# MCU.net
KiCad netlist of a schematic drawn in Altium Designer
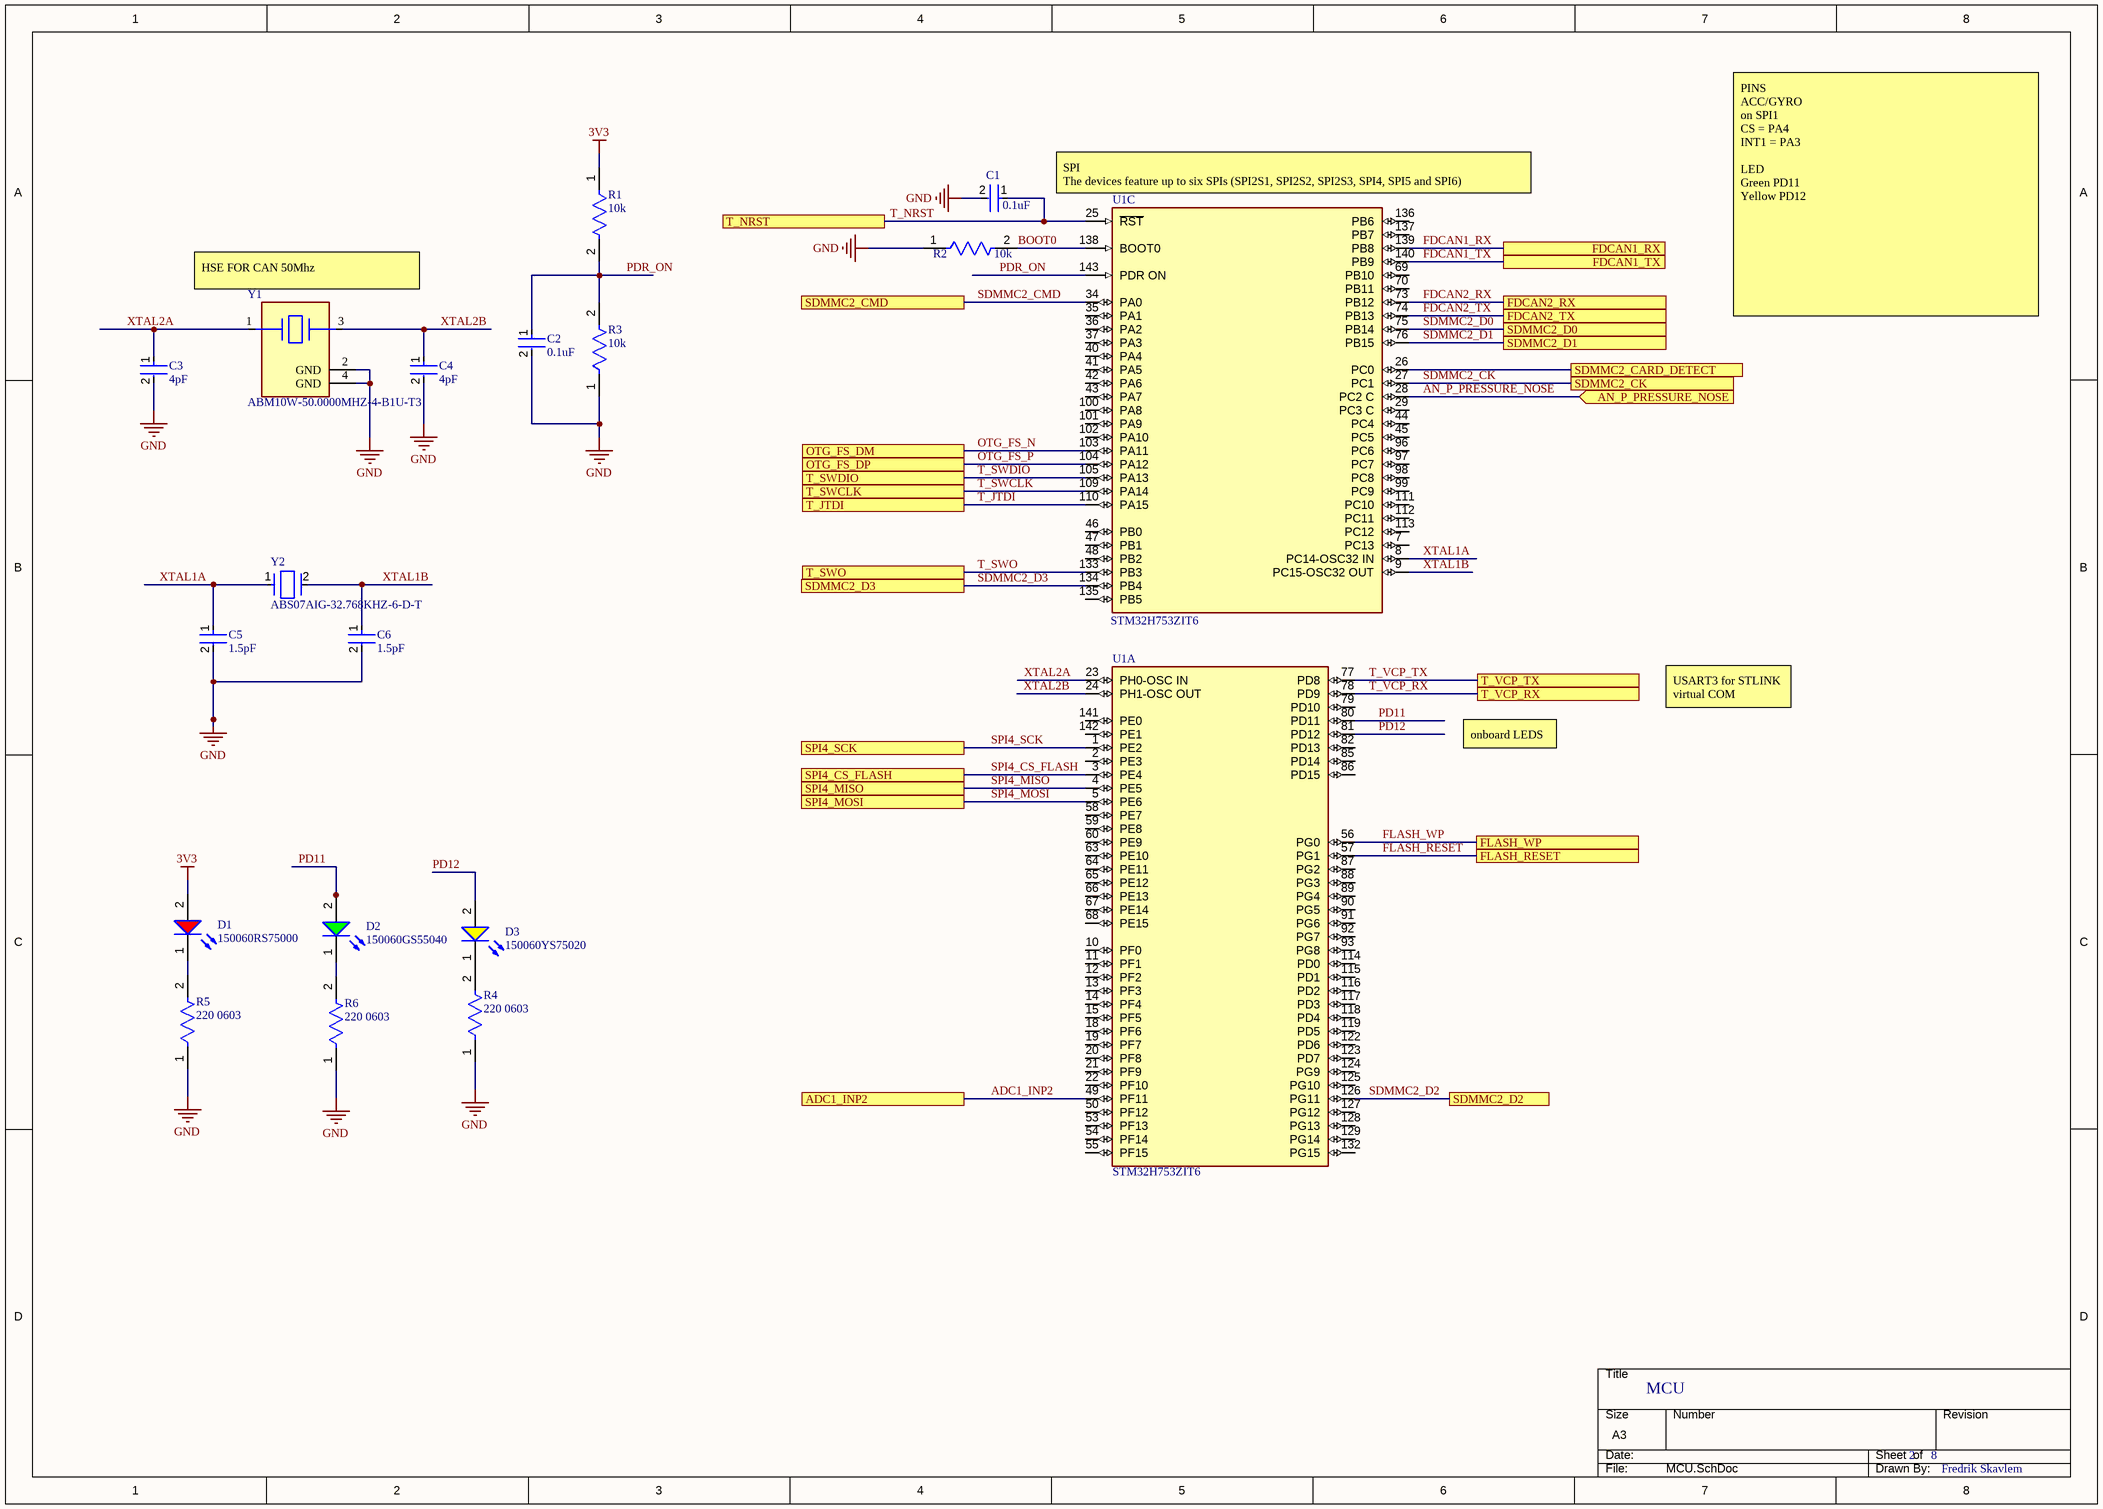
[diagram p0: MCU.SchDoc]

(export (version "E")
  (design (tool "Eeschema 10.0.6"))
  (components
    (comp (ref "C1")
      (value "0.1uF")
      (footprint "FP-CL10-IPC_C")
      (description "Cap Ceramic 100nF 16V X7R ±10% Pad SMD 0603 +125°C T/R\r\nCL10B104KO8WPNC")
      (fields (field (name "TOLERANCE") "10%"))
      (libsource (lib "Altium Content Vault") (part "b4654b650e69147ec39a6b967a45e02"))
    )
    (comp (ref "C2")
      (value "0.1uF")
      (footprint "FP-CL10-IPC_C")
      (description "Cap Ceramic 100nF 16V X7R ±10% Pad SMD 0603 +125°C T/R\r\nCL10B104KO8WPNC")
      (fields (field (name "TOLERANCE") "10%"))
      (libsource (lib "Altium Content Vault") (part "b4654b650e69147ec39a6b967a45e02"))
    )
    (comp (ref "C3")
      (value "4pF")
      (footprint "FP-GQM187-0_15-IPC_B")
      (description "GQM1875C2E4R0BB12D\r\nCeramic Capacitor 4pF ±0.1pF 250VDC C0G 0603 Paper T/R")
      (libsource (lib "Altium Content Vault") (part "02cd4be3c70576c341d710602a673aa"))
    )
    (comp (ref "C4")
      (value "4pF")
      (footprint "FP-GQM187-0_15-IPC_B")
      (description "GQM1875C2E4R0BB12D\r\nCeramic Capacitor 4pF ±0.1pF 250VDC C0G 0603 Paper T/R")
      (libsource (lib "Altium Content Vault") (part "02cd4be3c70576c341d710602a673aa"))
    )
    (comp (ref "C5")
      (value "1.5pF")
      (footprint "FP-C0603C-CF-IPC_C")
      (description "C0603 1.5 pF X8R 30ppm/°C 0.1 pF 25 V\r\nC0603C159B3HACTU")
      (fields
        (field (name "OCTOPART") "https://octopart.com/c0603c159b3hactu-kemet-88725126")
        (field (name "MANUFACTURER") "KEMET")
      )
      (libsource (lib "Altium Content Vault") (part "b4654b650e69147ec39a6b967a45e02"))
    )
    (comp (ref "C6")
      (value "1.5pF")
      (footprint "FP-C0603C-CF-MFG")
      (description "C0603 1.5 pF X8R 30ppm/°C 0.1 pF 25 V\r\nC0603C159B3HACTU")
      (fields
        (field (name "OCTOPART") "https://octopart.com/c0603c159b3hactu-kemet-88725126")
        (field (name "MANUFACTURER") "KEMET")
      )
      (libsource (lib "Altium Content Vault") (part "b4654b650e69147ec39a6b967a45e02"))
    )
    (comp (ref "D1")
      (value "150060RS75000")
      (footprint "WL-SMCW_0603_150060xx75000")
      (libsource (lib "Altium Content Vault") (part "LED_Red_2A-1K"))
    )
    (comp (ref "D2")
      (value "150060GS55040")
      (footprint "WL-SMCD_0603")
      (description "150060GS55040 WL-SMCD SMT Mono-color Chip LED Diffused")
      (libsource (lib "Altium Content Vault") (part "LED_Green_2A-1K"))
    )
    (comp (ref "D3")
      (value "150060YS75020")
      (footprint "WL-SMCW_0603_150060xx75020")
      (description "WL-SMCW SMT Mono-Color Chip LED Waterclear super f")
      (libsource (lib "Altium Content Vault") (part "LED_Yellow_2A-1K"))
    )
    (comp (ref "R1")
      (value "10k")
      (footprint "FP-RT0603-IPC_C")
      (description "RES SMD 10K OHM 1% 1/10W 0603\r\nRT0603FRE0710KL")
      (fields
        (field (name "MANUFACTURER") "Yageo")
        (field (name "OCTOPART") "https://octopart.com/rt0603fre0710kl-yageo-40009243")
      )
      (libsource (lib "Altium Content Vault") (part "1029c3af85768c4190bb7ad29bc67b5"))
    )
    (comp (ref "R2")
      (value "10k")
      (footprint "FP-RT0603-IPC_C")
      (description "RES SMD 10K OHM 1% 1/10W 0603\r\nRT0603FRE0710KL")
      (fields
        (field (name "MANUFACTURER") "Yageo")
        (field (name "OCTOPART") "https://octopart.com/rt0603fre0710kl-yageo-40009243")
      )
      (libsource (lib "Altium Content Vault") (part "1029c3af85768c4190bb7ad29bc67b5"))
    )
    (comp (ref "R3")
      (value "10k")
      (footprint "FP-RT0603-IPC_C")
      (description "RES SMD 10K OHM 1% 1/10W 0603\r\nRT0603FRE0710KL")
      (fields
        (field (name "MANUFACTURER") "Yageo")
        (field (name "OCTOPART") "https://octopart.com/rt0603fre0710kl-yageo-40009243")
      )
      (libsource (lib "Altium Content Vault") (part "1029c3af85768c4190bb7ad29bc67b5"))
    )
    (comp (ref "R4")
      (value "220 0603")
      (footprint "FP-AF0603-IPC_C")
      (description "AF0603JR-07220RL Anti-Sulfurated Chip Resistors Automotive Grade 220Ω 5% 100ppm/°C 0603")
      (fields (field (name "TOLERANCE") "5%"))
      (libsource (lib "Altium Content Vault") (part "1029c3af85768c4190bb7ad29bc67b5"))
    )
    (comp (ref "R5")
      (value "220 0603")
      (footprint "FP-AF0603-IPC_C")
      (description "AF0603JR-07220RL Anti-Sulfurated Chip Resistors Automotive Grade 220Ω 5% 100ppm/°C 0603")
      (fields (field (name "TOLERANCE") "5%"))
      (libsource (lib "Altium Content Vault") (part "1029c3af85768c4190bb7ad29bc67b5"))
    )
    (comp (ref "R6")
      (value "220 0603")
      (footprint "FP-AF0603-IPC_C")
      (description "AF0603JR-07220RL Anti-Sulfurated Chip Resistors Automotive Grade 220Ω 5% 100ppm/°C 0603")
      (fields (field (name "TOLERANCE") "5%"))
      (libsource (lib "Altium Content Vault") (part "1029c3af85768c4190bb7ad29bc67b5"))
    )
    (comp (ref "U1")
      (value "STM32H753ZIT6")
      (footprint "FP-LQFP144-1A-MFG")
      (description "LQFP 144 20X20X1.4 2")
      (fields
        (field (name "MANUFACTURER") "STMicroelectronics")
        (field (name "OCTOPART") "https://octopart.com/stm32h753zit6-stmicroelectronics-87879771")
      )
      (libsource (lib "Altium Content Vault") (part "eeed45f8b0ec3d8db28e558541eef73"))
    )
    (comp (ref "Y1")
      (value "ABM10W-50.0000MHZ-4-B1U-T3")
      (footprint "FP-ABM10W-MFG")
      (description "Crystal 50MHz ±10ppm 4pF SMD-4 2.5mm x 2mm")
      (libsource (lib "Altium Content Vault") (part "5d53a81b36bb19e40e9e80ec3e46f97"))
    )
    (comp (ref "Y2")
      (value "ABS07AIG-32.768KHZ-6-D-T")
      (footprint "FP-ABS07AIG-MFG")
      (description "Crystal 32.768kHz ±20ppm (Tol) 6pF FUND 70kΩ Automotive 2-Pin Mini-CSMD T/R")
      (libsource (lib "Altium Content Vault") (part "c23a69dc6c9e2f18f2079038eb95dd1"))
    )
  )
  (nets
    (net (code "1") (name "/ADC1_INP2") (class "Default")
      (node (ref "U1") (pin "49") (pinfunction "PF11_49") (pintype "bidirectional"))
    )
    (net (code "2") (name "/AN_P_PRESSURE_NOSE") (class "Default")
      (node (ref "U1") (pin "28") (pinfunction "PC2_C_28") (pintype "bidirectional"))
    )
    (net (code "3") (name "/BOOT0") (class "Default")
      (node (ref "R2") (pin "2") (pinfunction "2_2") (pintype "passive"))
      (node (ref "U1") (pin "138") (pinfunction "BOOT0_138") (pintype "input"))
    )
    (net (code "4") (name "/FDCAN1_RX") (class "Default")
      (node (ref "U1") (pin "139") (pinfunction "PB8_139") (pintype "bidirectional"))
    )
    (net (code "5") (name "/FDCAN1_TX") (class "Default")
      (node (ref "U1") (pin "140") (pinfunction "PB9_140") (pintype "bidirectional"))
    )
    (net (code "6") (name "/FDCAN2_RX") (class "Default")
      (node (ref "U1") (pin "73") (pinfunction "PB12_73") (pintype "bidirectional"))
    )
    (net (code "7") (name "/FDCAN2_TX") (class "Default")
      (node (ref "U1") (pin "74") (pinfunction "PB13_74") (pintype "bidirectional"))
    )
    (net (code "8") (name "/FLASH_RESET") (class "Default")
      (node (ref "U1") (pin "57") (pinfunction "PG1_57") (pintype "bidirectional"))
    )
    (net (code "9") (name "/FLASH_WP") (class "Default")
      (node (ref "U1") (pin "56") (pinfunction "PG0_56") (pintype "bidirectional"))
    )
    (net (code "10") (name "/OTG_FS_N") (class "Default")
      (node (ref "U1") (pin "103") (pinfunction "PA11_103") (pintype "bidirectional"))
    )
    (net (code "11") (name "/OTG_FS_P") (class "Default")
      (node (ref "U1") (pin "104") (pinfunction "PA12_104") (pintype "bidirectional"))
    )
    (net (code "12") (name "/PD11") (class "Default")
      (node (ref "D2") (pin "2") (pinfunction "A_2") (pintype "passive"))
      (node (ref "U1") (pin "80") (pinfunction "PD11_80") (pintype "bidirectional"))
    )
    (net (code "13") (name "/PD12") (class "Default")
      (node (ref "D3") (pin "2") (pinfunction "A_2") (pintype "passive"))
      (node (ref "U1") (pin "81") (pinfunction "PD12_81") (pintype "bidirectional"))
    )
    (net (code "14") (name "/PDR_ON") (class "Default")
      (node (ref "C2") (pin "1") (pinfunction "1_1") (pintype "passive"))
      (node (ref "R1") (pin "2") (pinfunction "2_2") (pintype "passive"))
      (node (ref "R3") (pin "2") (pinfunction "2_2") (pintype "passive"))
      (node (ref "U1") (pin "143") (pinfunction "PDR_ON_143") (pintype "input"))
    )
    (net (code "15") (name "/SDMMC2_CARD_DETECT") (class "Default")
      (node (ref "U1") (pin "26") (pinfunction "PC0_26") (pintype "bidirectional"))
    )
    (net (code "16") (name "/SDMMC2_CK") (class "Default")
      (node (ref "U1") (pin "27") (pinfunction "PC1_27") (pintype "bidirectional"))
    )
    (net (code "17") (name "/SDMMC2_CMD") (class "Default")
      (node (ref "U1") (pin "34") (pinfunction "PA0_34") (pintype "bidirectional"))
    )
    (net (code "18") (name "/SDMMC2_D0") (class "Default")
      (node (ref "U1") (pin "75") (pinfunction "PB14_75") (pintype "bidirectional"))
    )
    (net (code "19") (name "/SDMMC2_D1") (class "Default")
      (node (ref "U1") (pin "76") (pinfunction "PB15_76") (pintype "bidirectional"))
    )
    (net (code "20") (name "/SDMMC2_D2") (class "Default")
      (node (ref "U1") (pin "126") (pinfunction "PG11_126") (pintype "bidirectional"))
    )
    (net (code "21") (name "/SDMMC2_D3") (class "Default")
      (node (ref "U1") (pin "134") (pinfunction "PB4_134") (pintype "bidirectional"))
    )
    (net (code "22") (name "/SPI4_CS_FLASH") (class "Default")
      (node (ref "U1") (pin "3") (pinfunction "PE4_3") (pintype "bidirectional"))
    )
    (net (code "23") (name "/SPI4_MISO") (class "Default")
      (node (ref "U1") (pin "4") (pinfunction "PE5_4") (pintype "bidirectional"))
    )
    (net (code "24") (name "/SPI4_MOSI") (class "Default")
      (node (ref "U1") (pin "5") (pinfunction "PE6_5") (pintype "bidirectional"))
    )
    (net (code "25") (name "/SPI4_SCK") (class "Default")
      (node (ref "U1") (pin "1") (pinfunction "PE2_1") (pintype "bidirectional"))
    )
    (net (code "26") (name "/T_JTDI") (class "Default")
      (node (ref "U1") (pin "110") (pinfunction "PA15_110") (pintype "bidirectional"))
    )
    (net (code "27") (name "/T_NRST") (class "Default")
      (node (ref "C1") (pin "1") (pinfunction "1_1") (pintype "passive"))
      (node (ref "U1") (pin "25") (pinfunction "~{RST}_25") (pintype "input"))
    )
    (net (code "28") (name "/T_SWCLK") (class "Default")
      (node (ref "U1") (pin "109") (pinfunction "PA14_109") (pintype "bidirectional"))
    )
    (net (code "29") (name "/T_SWDIO") (class "Default")
      (node (ref "U1") (pin "105") (pinfunction "PA13_105") (pintype "bidirectional"))
    )
    (net (code "30") (name "/T_SWO") (class "Default")
      (node (ref "U1") (pin "133") (pinfunction "PB3_133") (pintype "bidirectional"))
    )
    (net (code "31") (name "/T_VCP_RX") (class "Default")
      (node (ref "U1") (pin "78") (pinfunction "PD9_78") (pintype "bidirectional"))
    )
    (net (code "32") (name "/T_VCP_TX") (class "Default")
      (node (ref "U1") (pin "77") (pinfunction "PD8_77") (pintype "bidirectional"))
    )
    (net (code "33") (name "/XTAL1A") (class "Default")
      (node (ref "C5") (pin "1") (pinfunction "1_1") (pintype "passive"))
      (node (ref "U1") (pin "8") (pinfunction "PC14-OSC32_IN_8") (pintype "bidirectional"))
      (node (ref "Y2") (pin "1") (pinfunction "1_1") (pintype "passive"))
    )
    (net (code "34") (name "/XTAL1B") (class "Default")
      (node (ref "C6") (pin "1") (pinfunction "1_1") (pintype "passive"))
      (node (ref "U1") (pin "9") (pinfunction "PC15-OSC32_OUT_9") (pintype "bidirectional"))
      (node (ref "Y2") (pin "2") (pinfunction "2_2") (pintype "passive"))
    )
    (net (code "35") (name "/XTAL2A") (class "Default")
      (node (ref "C3") (pin "1") (pinfunction "1_1") (pintype "passive"))
      (node (ref "U1") (pin "23") (pinfunction "PH0-OSC_IN_23") (pintype "bidirectional"))
      (node (ref "Y1") (pin "1") (pinfunction "1_1") (pintype "passive"))
    )
    (net (code "36") (name "/XTAL2B") (class "Default")
      (node (ref "C4") (pin "1") (pinfunction "1_1") (pintype "passive"))
      (node (ref "U1") (pin "24") (pinfunction "PH1-OSC_OUT_24") (pintype "bidirectional"))
      (node (ref "Y1") (pin "3") (pinfunction "3_3") (pintype "passive"))
    )
    (net (code "37") (name "3V3") (class "Default")
      (node (ref "D1") (pin "2") (pinfunction "A_2") (pintype "passive"))
      (node (ref "R1") (pin "1") (pinfunction "1_1") (pintype "passive"))
    )
    (net (code "38") (name "GND") (class "Default")
      (node (ref "C1") (pin "2") (pinfunction "2_2") (pintype "passive"))
      (node (ref "C2") (pin "2") (pinfunction "2_2") (pintype "passive"))
      (node (ref "C3") (pin "2") (pinfunction "2_2") (pintype "passive"))
      (node (ref "C4") (pin "2") (pinfunction "2_2") (pintype "passive"))
      (node (ref "C5") (pin "2") (pinfunction "2_2") (pintype "passive"))
      (node (ref "C6") (pin "2") (pinfunction "2_2") (pintype "passive"))
      (node (ref "R2") (pin "1") (pinfunction "1_1") (pintype "passive"))
      (node (ref "R3") (pin "1") (pinfunction "1_1") (pintype "passive"))
      (node (ref "R4") (pin "1") (pinfunction "1_1") (pintype "passive"))
      (node (ref "R5") (pin "1") (pinfunction "1_1") (pintype "passive"))
      (node (ref "R6") (pin "1") (pinfunction "1_1") (pintype "passive"))
      (node (ref "Y1") (pin "2") (pinfunction "GND_2") (pintype "power_in"))
      (node (ref "Y1") (pin "4") (pinfunction "GND_4") (pintype "power_in"))
    )
    (net (code "39") (name "Net-(D1-K)") (class "Default")
      (node (ref "D1") (pin "1") (pinfunction "K_1") (pintype "passive"))
      (node (ref "R5") (pin "2") (pinfunction "2_2") (pintype "passive"))
    )
    (net (code "40") (name "Net-(D2-K)") (class "Default")
      (node (ref "D2") (pin "1") (pinfunction "K_1") (pintype "passive"))
      (node (ref "R6") (pin "2") (pinfunction "2_2") (pintype "passive"))
    )
    (net (code "41") (name "Net-(D3-K)") (class "Default")
      (node (ref "D3") (pin "1") (pinfunction "K_1") (pintype "passive"))
      (node (ref "R4") (pin "2") (pinfunction "2_2") (pintype "passive"))
    )
    (net (code "42") (name "unconnected-(U1A-PD0-Pad114)") (class "Default")
      (node (ref "U1") (pin "114") (pinfunction "PD0_114") (pintype "bidirectional"))
    )
    (net (code "43") (name "unconnected-(U1A-PD1-Pad115)") (class "Default")
      (node (ref "U1") (pin "115") (pinfunction "PD1_115") (pintype "bidirectional"))
    )
    (net (code "44") (name "unconnected-(U1A-PD2-Pad116)") (class "Default")
      (node (ref "U1") (pin "116") (pinfunction "PD2_116") (pintype "bidirectional"))
    )
    (net (code "45") (name "unconnected-(U1A-PD3-Pad117)") (class "Default")
      (node (ref "U1") (pin "117") (pinfunction "PD3_117") (pintype "bidirectional"))
    )
    (net (code "46") (name "unconnected-(U1A-PD4-Pad118)") (class "Default")
      (node (ref "U1") (pin "118") (pinfunction "PD4_118") (pintype "bidirectional"))
    )
    (net (code "47") (name "unconnected-(U1A-PD5-Pad119)") (class "Default")
      (node (ref "U1") (pin "119") (pinfunction "PD5_119") (pintype "bidirectional"))
    )
    (net (code "48") (name "unconnected-(U1A-PD6-Pad122)") (class "Default")
      (node (ref "U1") (pin "122") (pinfunction "PD6_122") (pintype "bidirectional"))
    )
    (net (code "49") (name "unconnected-(U1A-PD7-Pad123)") (class "Default")
      (node (ref "U1") (pin "123") (pinfunction "PD7_123") (pintype "bidirectional"))
    )
    (net (code "50") (name "unconnected-(U1A-PD10-Pad79)") (class "Default")
      (node (ref "U1") (pin "79") (pinfunction "PD10_79") (pintype "bidirectional"))
    )
    (net (code "51") (name "unconnected-(U1A-PD13-Pad82)") (class "Default")
      (node (ref "U1") (pin "82") (pinfunction "PD13_82") (pintype "bidirectional"))
    )
    (net (code "52") (name "unconnected-(U1A-PD14-Pad85)") (class "Default")
      (node (ref "U1") (pin "85") (pinfunction "PD14_85") (pintype "bidirectional"))
    )
    (net (code "53") (name "unconnected-(U1A-PD15-Pad86)") (class "Default")
      (node (ref "U1") (pin "86") (pinfunction "PD15_86") (pintype "bidirectional"))
    )
    (net (code "54") (name "unconnected-(U1A-PE0-Pad141)") (class "Default")
      (node (ref "U1") (pin "141") (pinfunction "PE0_141") (pintype "bidirectional"))
    )
    (net (code "55") (name "unconnected-(U1A-PE1-Pad142)") (class "Default")
      (node (ref "U1") (pin "142") (pinfunction "PE1_142") (pintype "bidirectional"))
    )
    (net (code "56") (name "unconnected-(U1A-PE3-Pad2)") (class "Default")
      (node (ref "U1") (pin "2") (pinfunction "PE3_2") (pintype "bidirectional"))
    )
    (net (code "57") (name "unconnected-(U1A-PE7-Pad58)") (class "Default")
      (node (ref "U1") (pin "58") (pinfunction "PE7_58") (pintype "bidirectional"))
    )
    (net (code "58") (name "unconnected-(U1A-PE8-Pad59)") (class "Default")
      (node (ref "U1") (pin "59") (pinfunction "PE8_59") (pintype "bidirectional"))
    )
    (net (code "59") (name "unconnected-(U1A-PE9-Pad60)") (class "Default")
      (node (ref "U1") (pin "60") (pinfunction "PE9_60") (pintype "bidirectional"))
    )
    (net (code "60") (name "unconnected-(U1A-PE10-Pad63)") (class "Default")
      (node (ref "U1") (pin "63") (pinfunction "PE10_63") (pintype "bidirectional"))
    )
    (net (code "61") (name "unconnected-(U1A-PE11-Pad64)") (class "Default")
      (node (ref "U1") (pin "64") (pinfunction "PE11_64") (pintype "bidirectional"))
    )
    (net (code "62") (name "unconnected-(U1A-PE12-Pad65)") (class "Default")
      (node (ref "U1") (pin "65") (pinfunction "PE12_65") (pintype "bidirectional"))
    )
    (net (code "63") (name "unconnected-(U1A-PE13-Pad66)") (class "Default")
      (node (ref "U1") (pin "66") (pinfunction "PE13_66") (pintype "bidirectional"))
    )
    (net (code "64") (name "unconnected-(U1A-PE14-Pad67)") (class "Default")
      (node (ref "U1") (pin "67") (pinfunction "PE14_67") (pintype "bidirectional"))
    )
    (net (code "65") (name "unconnected-(U1A-PE15-Pad68)") (class "Default")
      (node (ref "U1") (pin "68") (pinfunction "PE15_68") (pintype "bidirectional"))
    )
    (net (code "66") (name "unconnected-(U1A-PF0-Pad10)") (class "Default")
      (node (ref "U1") (pin "10") (pinfunction "PF0_10") (pintype "bidirectional"))
    )
    (net (code "67") (name "unconnected-(U1A-PF1-Pad11)") (class "Default")
      (node (ref "U1") (pin "11") (pinfunction "PF1_11") (pintype "bidirectional"))
    )
    (net (code "68") (name "unconnected-(U1A-PF2-Pad12)") (class "Default")
      (node (ref "U1") (pin "12") (pinfunction "PF2_12") (pintype "bidirectional"))
    )
    (net (code "69") (name "unconnected-(U1A-PF3-Pad13)") (class "Default")
      (node (ref "U1") (pin "13") (pinfunction "PF3_13") (pintype "bidirectional"))
    )
    (net (code "70") (name "unconnected-(U1A-PF4-Pad14)") (class "Default")
      (node (ref "U1") (pin "14") (pinfunction "PF4_14") (pintype "bidirectional"))
    )
    (net (code "71") (name "unconnected-(U1A-PF5-Pad15)") (class "Default")
      (node (ref "U1") (pin "15") (pinfunction "PF5_15") (pintype "bidirectional"))
    )
    (net (code "72") (name "unconnected-(U1A-PF6-Pad18)") (class "Default")
      (node (ref "U1") (pin "18") (pinfunction "PF6_18") (pintype "bidirectional"))
    )
    (net (code "73") (name "unconnected-(U1A-PF7-Pad19)") (class "Default")
      (node (ref "U1") (pin "19") (pinfunction "PF7_19") (pintype "bidirectional"))
    )
    (net (code "74") (name "unconnected-(U1A-PF8-Pad20)") (class "Default")
      (node (ref "U1") (pin "20") (pinfunction "PF8_20") (pintype "bidirectional"))
    )
    (net (code "75") (name "unconnected-(U1A-PF9-Pad21)") (class "Default")
      (node (ref "U1") (pin "21") (pinfunction "PF9_21") (pintype "bidirectional"))
    )
    (net (code "76") (name "unconnected-(U1A-PF10-Pad22)") (class "Default")
      (node (ref "U1") (pin "22") (pinfunction "PF10_22") (pintype "bidirectional"))
    )
    (net (code "77") (name "unconnected-(U1A-PF12-Pad50)") (class "Default")
      (node (ref "U1") (pin "50") (pinfunction "PF12_50") (pintype "bidirectional"))
    )
    (net (code "78") (name "unconnected-(U1A-PF13-Pad53)") (class "Default")
      (node (ref "U1") (pin "53") (pinfunction "PF13_53") (pintype "bidirectional"))
    )
    (net (code "79") (name "unconnected-(U1A-PF14-Pad54)") (class "Default")
      (node (ref "U1") (pin "54") (pinfunction "PF14_54") (pintype "bidirectional"))
    )
    (net (code "80") (name "unconnected-(U1A-PF15-Pad55)") (class "Default")
      (node (ref "U1") (pin "55") (pinfunction "PF15_55") (pintype "bidirectional"))
    )
    (net (code "81") (name "unconnected-(U1A-PG2-Pad87)") (class "Default")
      (node (ref "U1") (pin "87") (pinfunction "PG2_87") (pintype "bidirectional"))
    )
    (net (code "82") (name "unconnected-(U1A-PG3-Pad88)") (class "Default")
      (node (ref "U1") (pin "88") (pinfunction "PG3_88") (pintype "bidirectional"))
    )
    (net (code "83") (name "unconnected-(U1A-PG4-Pad89)") (class "Default")
      (node (ref "U1") (pin "89") (pinfunction "PG4_89") (pintype "bidirectional"))
    )
    (net (code "84") (name "unconnected-(U1A-PG5-Pad90)") (class "Default")
      (node (ref "U1") (pin "90") (pinfunction "PG5_90") (pintype "bidirectional"))
    )
    (net (code "85") (name "unconnected-(U1A-PG6-Pad91)") (class "Default")
      (node (ref "U1") (pin "91") (pinfunction "PG6_91") (pintype "bidirectional"))
    )
    (net (code "86") (name "unconnected-(U1A-PG7-Pad92)") (class "Default")
      (node (ref "U1") (pin "92") (pinfunction "PG7_92") (pintype "bidirectional"))
    )
    (net (code "87") (name "unconnected-(U1A-PG8-Pad93)") (class "Default")
      (node (ref "U1") (pin "93") (pinfunction "PG8_93") (pintype "bidirectional"))
    )
    (net (code "88") (name "unconnected-(U1A-PG9-Pad124)") (class "Default")
      (node (ref "U1") (pin "124") (pinfunction "PG9_124") (pintype "bidirectional"))
    )
    (net (code "89") (name "unconnected-(U1A-PG10-Pad125)") (class "Default")
      (node (ref "U1") (pin "125") (pinfunction "PG10_125") (pintype "bidirectional"))
    )
    (net (code "90") (name "unconnected-(U1A-PG12-Pad127)") (class "Default")
      (node (ref "U1") (pin "127") (pinfunction "PG12_127") (pintype "bidirectional"))
    )
    (net (code "91") (name "unconnected-(U1A-PG13-Pad128)") (class "Default")
      (node (ref "U1") (pin "128") (pinfunction "PG13_128") (pintype "bidirectional"))
    )
    (net (code "92") (name "unconnected-(U1A-PG14-Pad129)") (class "Default")
      (node (ref "U1") (pin "129") (pinfunction "PG14_129") (pintype "bidirectional"))
    )
    (net (code "93") (name "unconnected-(U1A-PG15-Pad132)") (class "Default")
      (node (ref "U1") (pin "132") (pinfunction "PG15_132") (pintype "bidirectional"))
    )
    (net (code "94") (name "unconnected-(U1C-PA1-Pad35)") (class "Default")
      (node (ref "U1") (pin "35") (pinfunction "PA1_35") (pintype "bidirectional"))
    )
    (net (code "95") (name "unconnected-(U1C-PA2-Pad36)") (class "Default")
      (node (ref "U1") (pin "36") (pinfunction "PA2_36") (pintype "bidirectional"))
    )
    (net (code "96") (name "unconnected-(U1C-PA3-Pad37)") (class "Default")
      (node (ref "U1") (pin "37") (pinfunction "PA3_37") (pintype "bidirectional"))
    )
    (net (code "97") (name "unconnected-(U1C-PA4-Pad40)") (class "Default")
      (node (ref "U1") (pin "40") (pinfunction "PA4_40") (pintype "bidirectional"))
    )
    (net (code "98") (name "unconnected-(U1C-PA5-Pad41)") (class "Default")
      (node (ref "U1") (pin "41") (pinfunction "PA5_41") (pintype "bidirectional"))
    )
    (net (code "99") (name "unconnected-(U1C-PA6-Pad42)") (class "Default")
      (node (ref "U1") (pin "42") (pinfunction "PA6_42") (pintype "bidirectional"))
    )
    (net (code "100") (name "unconnected-(U1C-PA7-Pad43)") (class "Default")
      (node (ref "U1") (pin "43") (pinfunction "PA7_43") (pintype "bidirectional"))
    )
    (net (code "101") (name "unconnected-(U1C-PA8-Pad100)") (class "Default")
      (node (ref "U1") (pin "100") (pinfunction "PA8_100") (pintype "bidirectional"))
    )
    (net (code "102") (name "unconnected-(U1C-PA9-Pad101)") (class "Default")
      (node (ref "U1") (pin "101") (pinfunction "PA9_101") (pintype "bidirectional"))
    )
    (net (code "103") (name "unconnected-(U1C-PA10-Pad102)") (class "Default")
      (node (ref "U1") (pin "102") (pinfunction "PA10_102") (pintype "bidirectional"))
    )
    (net (code "104") (name "unconnected-(U1C-PB0-Pad46)") (class "Default")
      (node (ref "U1") (pin "46") (pinfunction "PB0_46") (pintype "bidirectional"))
    )
    (net (code "105") (name "unconnected-(U1C-PB1-Pad47)") (class "Default")
      (node (ref "U1") (pin "47") (pinfunction "PB1_47") (pintype "bidirectional"))
    )
    (net (code "106") (name "unconnected-(U1C-PB2-Pad48)") (class "Default")
      (node (ref "U1") (pin "48") (pinfunction "PB2_48") (pintype "bidirectional"))
    )
    (net (code "107") (name "unconnected-(U1C-PB5-Pad135)") (class "Default")
      (node (ref "U1") (pin "135") (pinfunction "PB5_135") (pintype "bidirectional"))
    )
    (net (code "108") (name "unconnected-(U1C-PB6-Pad136)") (class "Default")
      (node (ref "U1") (pin "136") (pinfunction "PB6_136") (pintype "bidirectional"))
    )
    (net (code "109") (name "unconnected-(U1C-PB7-Pad137)") (class "Default")
      (node (ref "U1") (pin "137") (pinfunction "PB7_137") (pintype "bidirectional"))
    )
    (net (code "110") (name "unconnected-(U1C-PB10-Pad69)") (class "Default")
      (node (ref "U1") (pin "69") (pinfunction "PB10_69") (pintype "bidirectional"))
    )
    (net (code "111") (name "unconnected-(U1C-PB11-Pad70)") (class "Default")
      (node (ref "U1") (pin "70") (pinfunction "PB11_70") (pintype "bidirectional"))
    )
    (net (code "112") (name "unconnected-(U1C-PC3_C-Pad29)") (class "Default")
      (node (ref "U1") (pin "29") (pinfunction "PC3_C_29") (pintype "bidirectional"))
    )
    (net (code "113") (name "unconnected-(U1C-PC4-Pad44)") (class "Default")
      (node (ref "U1") (pin "44") (pinfunction "PC4_44") (pintype "bidirectional"))
    )
    (net (code "114") (name "unconnected-(U1C-PC5-Pad45)") (class "Default")
      (node (ref "U1") (pin "45") (pinfunction "PC5_45") (pintype "bidirectional"))
    )
    (net (code "115") (name "unconnected-(U1C-PC6-Pad96)") (class "Default")
      (node (ref "U1") (pin "96") (pinfunction "PC6_96") (pintype "bidirectional"))
    )
    (net (code "116") (name "unconnected-(U1C-PC7-Pad97)") (class "Default")
      (node (ref "U1") (pin "97") (pinfunction "PC7_97") (pintype "bidirectional"))
    )
    (net (code "117") (name "unconnected-(U1C-PC8-Pad98)") (class "Default")
      (node (ref "U1") (pin "98") (pinfunction "PC8_98") (pintype "bidirectional"))
    )
    (net (code "118") (name "unconnected-(U1C-PC9-Pad99)") (class "Default")
      (node (ref "U1") (pin "99") (pinfunction "PC9_99") (pintype "bidirectional"))
    )
    (net (code "119") (name "unconnected-(U1C-PC10-Pad111)") (class "Default")
      (node (ref "U1") (pin "111") (pinfunction "PC10_111") (pintype "bidirectional"))
    )
    (net (code "120") (name "unconnected-(U1C-PC11-Pad112)") (class "Default")
      (node (ref "U1") (pin "112") (pinfunction "PC11_112") (pintype "bidirectional"))
    )
    (net (code "121") (name "unconnected-(U1C-PC12-Pad113)") (class "Default")
      (node (ref "U1") (pin "113") (pinfunction "PC12_113") (pintype "bidirectional"))
    )
    (net (code "122") (name "unconnected-(U1C-PC13-Pad7)") (class "Default")
      (node (ref "U1") (pin "7") (pinfunction "PC13_7") (pintype "bidirectional"))
    )
  )
)
